# LED-board-bottom.net
KiCad netlist of a schematic drawn in EAGLE
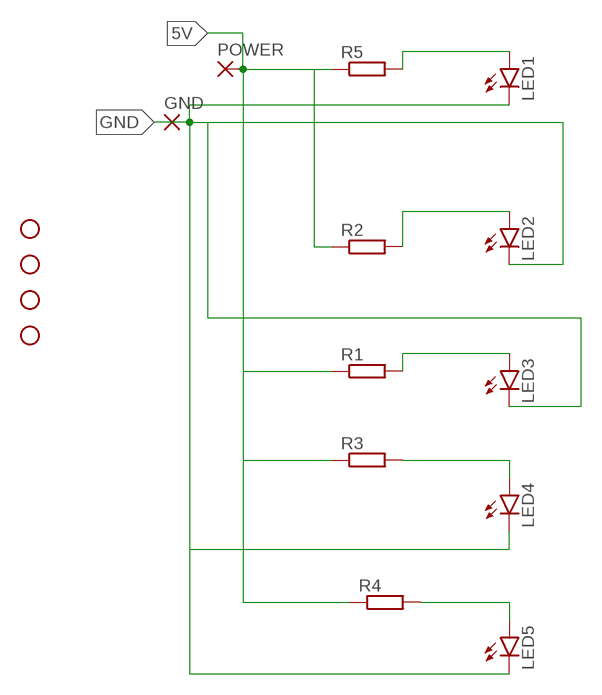
[diagram p0: schematic, sheet 1]

(export (version "E")
  (design (tool "Eeschema 10.0.6"))
  (components
    (comp (ref "GND")
      (value "1,6/0,8")
      (footprint "eagle-import:1,6_0,8")
      (libsource (lib "eagle-import") (part "1,6/0,8"))
    )
    (comp (ref "H1")
      (value "STAND-OFF")
      (footprint "eagle-import:STAND-OFF")
      (libsource (lib "eagle-import") (part "STAND-OFF"))
    )
    (comp (ref "H2")
      (value "STAND-OFF")
      (footprint "eagle-import:STAND-OFF")
      (libsource (lib "eagle-import") (part "STAND-OFF"))
    )
    (comp (ref "H3")
      (value "STAND-OFF")
      (footprint "eagle-import:STAND-OFF")
      (libsource (lib "eagle-import") (part "STAND-OFF"))
    )
    (comp (ref "H4")
      (value "STAND-OFF")
      (footprint "eagle-import:STAND-OFF")
      (libsource (lib "eagle-import") (part "STAND-OFF"))
    )
    (comp (ref "LED1")
      (value "LED3MM")
      (footprint "eagle-import:LED3MM")
      (libsource (lib "eagle-import") (part "LED3MM"))
    )
    (comp (ref "LED2")
      (value "LED3MM")
      (footprint "eagle-import:LED3MM")
      (libsource (lib "eagle-import") (part "LED3MM"))
    )
    (comp (ref "LED3")
      (value "LED3MM")
      (footprint "eagle-import:LED3MM")
      (libsource (lib "eagle-import") (part "LED3MM"))
    )
    (comp (ref "LED4")
      (value "LED3MM")
      (footprint "eagle-import:LED3MM")
      (libsource (lib "eagle-import") (part "LED3MM"))
    )
    (comp (ref "LED5")
      (value "LED3MM")
      (footprint "eagle-import:LED3MM")
      (libsource (lib "eagle-import") (part "LED3MM"))
    )
    (comp (ref "POWER")
      (value "1,6/0,8")
      (footprint "eagle-import:1,6_0,8")
      (libsource (lib "eagle-import") (part "1,6/0,8"))
    )
    (comp (ref "R1")
      (value "R-EU_0207/10")
      (footprint "eagle-import:0207_10")
      (libsource (lib "eagle-import") (part "R-EU_0207/10"))
    )
    (comp (ref "R2")
      (value "R-EU_0207/10")
      (footprint "eagle-import:0207_10")
      (libsource (lib "eagle-import") (part "R-EU_0207/10"))
    )
    (comp (ref "R3")
      (value "R-EU_0207/10")
      (footprint "eagle-import:0207_10")
      (libsource (lib "eagle-import") (part "R-EU_0207/10"))
    )
    (comp (ref "R4")
      (value "R-EU_0207/10")
      (footprint "eagle-import:0207_10")
      (libsource (lib "eagle-import") (part "R-EU_0207/10"))
    )
    (comp (ref "R5")
      (value "R-EU_0207/10")
      (footprint "eagle-import:0207_10")
      (libsource (lib "eagle-import") (part "R-EU_0207/10"))
    )
  )
  (nets
    (net (code "1") (name "5V") (class "Default")
      (node (ref "POWER") (pin "1") (pinfunction "P_1") (pintype "passive"))
      (node (ref "R1") (pin "1") (pinfunction "1_1") (pintype "passive"))
      (node (ref "R2") (pin "1") (pinfunction "1_1") (pintype "passive"))
      (node (ref "R3") (pin "1") (pinfunction "1_1") (pintype "passive"))
      (node (ref "R4") (pin "1") (pinfunction "1_1") (pintype "passive"))
      (node (ref "R5") (pin "1") (pinfunction "1_1") (pintype "passive"))
    )
    (net (code "2") (name "GND") (class "Default")
      (node (ref "GND") (pin "1") (pinfunction "P_1") (pintype "passive"))
      (node (ref "LED1") (pin "K") (pinfunction "C_K") (pintype "passive"))
      (node (ref "LED2") (pin "K") (pinfunction "C_K") (pintype "passive"))
      (node (ref "LED3") (pin "K") (pinfunction "C_K") (pintype "passive"))
      (node (ref "LED4") (pin "K") (pinfunction "C_K") (pintype "passive"))
      (node (ref "LED5") (pin "K") (pinfunction "C_K") (pintype "passive"))
    )
    (net (code "3") (name "Net-(LED1-PadA)") (class "Default")
      (node (ref "LED1") (pin "A") (pinfunction "A_A") (pintype "passive"))
      (node (ref "R5") (pin "2") (pinfunction "2_2") (pintype "passive"))
    )
    (net (code "4") (name "Net-(LED2-PadA)") (class "Default")
      (node (ref "LED2") (pin "A") (pinfunction "A_A") (pintype "passive"))
      (node (ref "R2") (pin "2") (pinfunction "2_2") (pintype "passive"))
    )
    (net (code "5") (name "Net-(LED3-PadA)") (class "Default")
      (node (ref "LED3") (pin "A") (pinfunction "A_A") (pintype "passive"))
      (node (ref "R1") (pin "2") (pinfunction "2_2") (pintype "passive"))
    )
    (net (code "6") (name "Net-(LED4-PadA)") (class "Default")
      (node (ref "LED4") (pin "A") (pinfunction "A_A") (pintype "passive"))
      (node (ref "R3") (pin "2") (pinfunction "2_2") (pintype "passive"))
    )
    (net (code "7") (name "Net-(LED5-PadA)") (class "Default")
      (node (ref "LED5") (pin "A") (pinfunction "A_A") (pintype "passive"))
      (node (ref "R4") (pin "2") (pinfunction "2_2") (pintype "passive"))
    )
  )
)
